# Schematic.net
KiCad netlist of a schematic drawn in Altium Designer
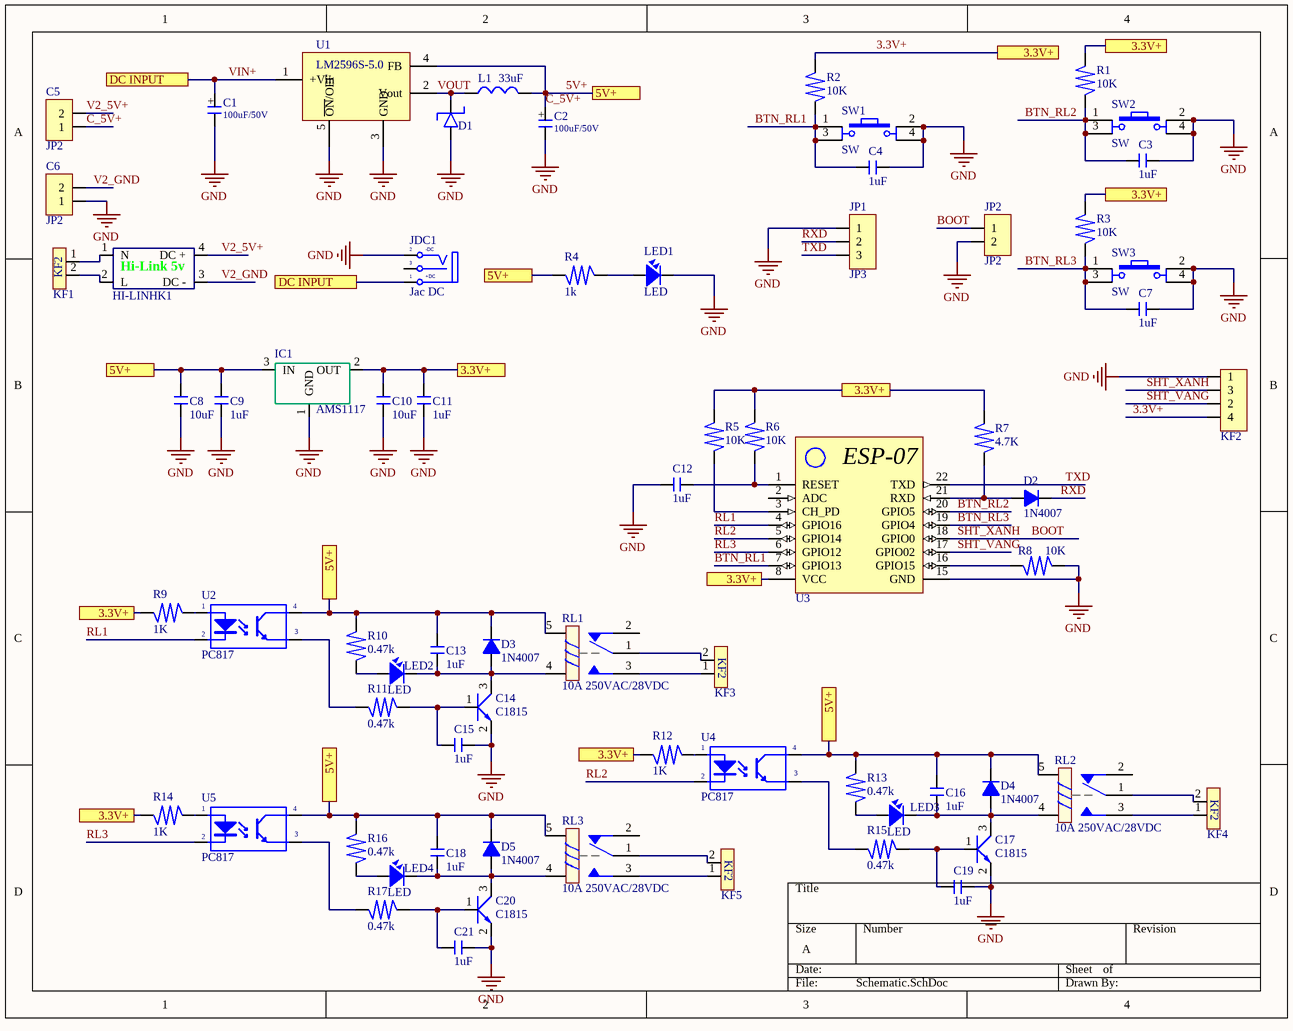
[diagram p0: Schematic.SchDoc]

(export (version "E")
  (design (tool "Eeschema 10.0.6"))
  (components
    (comp (ref "C1")
      (value "100uF/50V")
      (footprint "ALU D8x10")
      (description "100UF 50V, 20%, Size D=8mm, L=10mm")
      (fields (field (name "Comment") "CAP ALUM 100UF 50V 20% SMD"))
      (libsource (lib "LibSchQuocBao") (part "Alu 100uF/50v"))
    )
    (comp (ref "C2")
      (value "100uF/50V")
      (footprint "ALU D8x10")
      (description "100UF 50V, 20%, Size D=8mm, L=10mm")
      (fields (field (name "Comment") "CAP ALUM 100UF 50V 20% SMD"))
      (libsource (lib "LibSchQuocBao") (part "Alu 100uF/50v"))
    )
    (comp (ref "C3")
      (value "1uF")
      (footprint "C 0603(1608 metric)")
      (description "Capacitors Size SMD 0603")
      (libsource (lib "LibSchQuocBao") (part "CAP 0603 SMD"))
    )
    (comp (ref "C4")
      (value "1uF")
      (footprint "C 0603(1608 metric)")
      (description "Capacitors Size SMD 0603")
      (libsource (lib "LibSchQuocBao") (part "CAP 0603 SMD"))
    )
    (comp (ref "C5")
      (value "JP2")
      (footprint "JP2-CLOSED")
      (description "WR-PHD 2.54 mm Angled Socket Header")
      (fields
        (field (name "MANUFACTURER") "Würth Elektronik eiSos GmbH")
        (field (name "PARTNO") "613002143121")
        (field (name "CREATED BY") "Karrer Zheng")
      )
      (libsource (lib "LibSchQuocBao") (part "JP2"))
    )
    (comp (ref "C6")
      (value "JP2")
      (footprint "JP2-CLOSED")
      (description "WR-PHD 2.54 mm Angled Socket Header")
      (fields
        (field (name "MANUFACTURER") "Würth Elektronik eiSos GmbH")
        (field (name "PARTNO") "613002143121")
        (field (name "CREATED BY") "Karrer Zheng")
      )
      (libsource (lib "LibSchQuocBao") (part "JP2"))
    )
    (comp (ref "C7")
      (value "1uF")
      (footprint "C 0603(1608 metric)")
      (description "Capacitors Size SMD 0603")
      (libsource (lib "LibSchQuocBao") (part "CAP 0603 SMD"))
    )
    (comp (ref "C8")
      (value "10uF")
      (footprint "C 0603(1608 metric)")
      (description "Capacitors Size SMD 0603")
      (libsource (lib "LibSchQuocBao") (part "CAP 0603 SMD"))
    )
    (comp (ref "C9")
      (value "1uF")
      (footprint "C 0603(1608 metric)")
      (description "Capacitors Size SMD 0603")
      (libsource (lib "LibSchQuocBao") (part "CAP 0603 SMD"))
    )
    (comp (ref "C10")
      (value "10uF")
      (footprint "C 0603(1608 metric)")
      (description "Capacitors Size SMD 0603")
      (libsource (lib "LibSchQuocBao") (part "CAP 0603 SMD"))
    )
    (comp (ref "C11")
      (value "1uF")
      (footprint "C 0603(1608 metric)")
      (description "Capacitors Size SMD 0603")
      (libsource (lib "LibSchQuocBao") (part "CAP 0603 SMD"))
    )
    (comp (ref "C12")
      (value "1uF")
      (footprint "C 0603(1608 metric)")
      (description "Capacitors Size SMD 0603")
      (libsource (lib "LibSchQuocBao") (part "CAP 0603 SMD"))
    )
    (comp (ref "C13")
      (value "1uF")
      (footprint "C 0603(1608 metric)")
      (description "Capacitors Size SMD 0603")
      (libsource (lib "LibSchQuocBao") (part "CAP 0603 SMD"))
    )
    (comp (ref "C14")
      (value "C1815")
      (footprint "SOT23")
      (description "NPN ECB transistor, SOT23-3 package")
      (libsource (lib "LibSchQuocBao") (part "C1815 2SC1815-HF"))
    )
    (comp (ref "C15")
      (value "1uF")
      (footprint "C 0603(1608 metric)")
      (description "Capacitors Size SMD 0603")
      (libsource (lib "LibSchQuocBao") (part "CAP 0603 SMD"))
    )
    (comp (ref "C16")
      (value "1uF")
      (footprint "C 0603(1608 metric)")
      (description "Capacitors Size SMD 0603")
      (libsource (lib "LibSchQuocBao") (part "CAP 0603 SMD"))
    )
    (comp (ref "C17")
      (value "C1815")
      (footprint "SOT23")
      (description "NPN ECB transistor, SOT23-3 package")
      (libsource (lib "LibSchQuocBao") (part "C1815 2SC1815-HF"))
    )
    (comp (ref "C18")
      (value "1uF")
      (footprint "C 0603(1608 metric)")
      (description "Capacitors Size SMD 0603")
      (libsource (lib "LibSchQuocBao") (part "CAP 0603 SMD"))
    )
    (comp (ref "C19")
      (value "1uF")
      (footprint "C 0603(1608 metric)")
      (description "Capacitors Size SMD 0603")
      (libsource (lib "LibSchQuocBao") (part "CAP 0603 SMD"))
    )
    (comp (ref "C20")
      (value "C1815")
      (footprint "SOT23")
      (description "NPN ECB transistor, SOT23-3 package")
      (libsource (lib "LibSchQuocBao") (part "C1815 2SC1815-HF"))
    )
    (comp (ref "C21")
      (value "1uF")
      (footprint "C 0603(1608 metric)")
      (description "Capacitors Size SMD 0603")
      (libsource (lib "LibSchQuocBao") (part "CAP 0603 SMD"))
    )
    (comp (ref "D1")
      (value "SS34 SMA")
      (footprint "SS34-SMA")
      (description "Size A, DIODE SCHOTTKY 3A 40V SMA")
      (libsource (lib "LibSchQuocBao") (part "SS34 SMA"))
    )
    (comp (ref "D2")
      (value "1N4007")
      (footprint "SMA")
      (description "Diode 1A")
      (libsource (lib "LibSchQuocBao") (part "diode"))
    )
    (comp (ref "D3")
      (value "1N4007")
      (footprint "SMA")
      (description "Diode 1A")
      (libsource (lib "LibSchQuocBao") (part "diode"))
    )
    (comp (ref "D4")
      (value "1N4007")
      (footprint "SMA")
      (description "Diode 1A")
      (libsource (lib "LibSchQuocBao") (part "diode"))
    )
    (comp (ref "D5")
      (value "1N4007")
      (footprint "SMA")
      (description "Diode 1A")
      (libsource (lib "LibSchQuocBao") (part "diode"))
    )
    (comp (ref "HI-LINHK1")
      (value "Hi-link 5v")
      (footprint "Hi-Link")
      (libsource (lib "LibSchQuocBao") (part "Hi-link 5v"))
    )
    (comp (ref "IC1")
      (value "AMS1117")
      (footprint "AMS-1117")
      (libsource (lib "LibSchQuocBao") (part "AMS1117 3.3V"))
    )
    (comp (ref "JDC1")
      (value "Jac DC")
      (footprint "DC-IN")
      (description "Jac DC input")
      (libsource (lib "LibSchQuocBao") (part "DCIN"))
    )
    (comp (ref "JP1")
      (value "JP3")
      (footprint "JP3-D1T")
      (description "WR-PHD 2.54 mm Angled Socket Header")
      (fields
        (field (name "MANUFACTURER") "Würth Elektronik eiSos GmbH")
        (field (name "PARTNO") "613003143121")
        (field (name "CREATED BY") "Karrer Zheng")
      )
      (libsource (lib "LibSchQuocBao") (part "JP3"))
    )
    (comp (ref "JP2")
      (value "JP2")
      (footprint "JP2-CLOSED")
      (description "WR-PHD 2.54 mm Angled Socket Header")
      (fields
        (field (name "MANUFACTURER") "Würth Elektronik eiSos GmbH")
        (field (name "PARTNO") "613002143121")
        (field (name "CREATED BY") "Karrer Zheng")
      )
      (libsource (lib "") (part "JP2_1"))
    )
    (comp (ref "KF1")
      (value "Terminal Block 2Pin 5.08  KF2EDGK-5.08-2P-L")
      (footprint "KF2-7.62")
      (description "KF2 7.62")
      (libsource (lib "") (part "KF2_1"))
    )
    (comp (ref "KF2")
      (value "Terminal Block 4Pin 5.08  KF4EDGK-5.08-24-L")
      (footprint "HED4T")
      (libsource (lib "LibSchQuocBao") (part "KF4(KF4EDGK-5.08-4P-L)_1"))
    )
    (comp (ref "KF3")
      (value "Terminal Block 2Pin 5.08  KF2EDGK-5.08-2P-L")
      (footprint "KF2-7.62")
      (description "KF2 7.62")
      (libsource (lib "LibSchQuocBao") (part "KF2"))
    )
    (comp (ref "KF4")
      (value "Terminal Block 2Pin 5.08  KF2EDGK-5.08-2P-L")
      (footprint "KF2-7.62")
      (description "KF2 7.62")
      (libsource (lib "LibSchQuocBao") (part "KF2"))
    )
    (comp (ref "KF5")
      (value "Terminal Block 2Pin 5.08  KF2EDGK-5.08-2P-L")
      (footprint "KF2-7.62")
      (description "KF2 7.62")
      (libsource (lib "LibSchQuocBao") (part "KF2"))
    )
    (comp (ref "L1")
      (value "33uF")
      (footprint "RH127-471")
      (description "33UH (330) 3A, Size 12x12x7mm")
      (libsource (lib "LibSchQuocBao") (part "L 33UH RH127"))
    )
    (comp (ref "LED1")
      (value "LED")
      (footprint "LED-3")
      (description "LED Single colour Green and Red")
      (libsource (lib "LibSchQuocBao") (part "LED-DIP"))
    )
    (comp (ref "LED2")
      (value "LED")
      (footprint "LED-3")
      (description "LED Single colour Green and Red")
      (libsource (lib "LibSchQuocBao") (part "LED-DIP"))
    )
    (comp (ref "LED3")
      (value "LED")
      (footprint "LED-3")
      (description "LED Single colour Green and Red")
      (libsource (lib "LibSchQuocBao") (part "LED-DIP"))
    )
    (comp (ref "LED4")
      (value "LED")
      (footprint "LED-3")
      (description "LED Single colour Green and Red")
      (libsource (lib "LibSchQuocBao") (part "LED-DIP"))
    )
    (comp (ref "R1")
      (value "10K")
      (footprint "RES_0603")
      (description "SMD Resistor 3k OHM (Code 103) 1/8W 5% 0805 SMD")
      (fields (field (name "Comment") "RES 0.3K Ohm 0805 5%"))
      (libsource (lib "LibSchQuocBao") (part "R-0603-1k 5%"))
    )
    (comp (ref "R2")
      (value "10K")
      (footprint "RES_0603")
      (description "SMD Resistor 3k OHM (Code 103) 1/8W 5% 0805 SMD")
      (fields (field (name "Comment") "RES 0.3K Ohm 0805 5%"))
      (libsource (lib "LibSchQuocBao") (part "R-0603-1k 5%"))
    )
    (comp (ref "R3")
      (value "10K")
      (footprint "RES_0603")
      (description "SMD Resistor 3k OHM (Code 103) 1/8W 5% 0805 SMD")
      (fields (field (name "Comment") "RES 0.3K Ohm 0805 5%"))
      (libsource (lib "LibSchQuocBao") (part "R-0603-1k 5%"))
    )
    (comp (ref "R4")
      (value "1k")
      (footprint "RES_0603")
      (description "SMD Resistor 3k OHM (Code 103) 1/8W 5% 0805 SMD")
      (fields (field (name "Comment") "RES 0.3K Ohm 0805 5%"))
      (libsource (lib "LibSchQuocBao") (part "R-0603-1k 5%"))
    )
    (comp (ref "R5")
      (value "10K")
      (footprint "RES_0603")
      (description "SMD Resistor 3k OHM (Code 103) 1/8W 5% 0805 SMD")
      (fields (field (name "Comment") "RES 0.3K Ohm 0805 5%"))
      (libsource (lib "LibSchQuocBao") (part "R-0603-1k 5%"))
    )
    (comp (ref "R6")
      (value "10K")
      (footprint "RES_0603")
      (description "SMD Resistor 3k OHM (Code 103) 1/8W 5% 0805 SMD")
      (fields (field (name "Comment") "RES 0.3K Ohm 0805 5%"))
      (libsource (lib "LibSchQuocBao") (part "R-0603-1k 5%"))
    )
    (comp (ref "R7")
      (value "4.7K")
      (footprint "RES_0603")
      (description "SMD Resistor 3k OHM (Code 103) 1/8W 5% 0805 SMD")
      (fields (field (name "Comment") "RES 0.3K Ohm 0805 5%"))
      (libsource (lib "LibSchQuocBao") (part "R-0603-1k 5%"))
    )
    (comp (ref "R8")
      (value "10K")
      (footprint "RES_0603")
      (description "SMD Resistor 3k OHM (Code 103) 1/8W 5% 0805 SMD")
      (fields (field (name "Comment") "RES 0.3K Ohm 0805 5%"))
      (libsource (lib "LibSchQuocBao") (part "R-0603-1k 5%"))
    )
    (comp (ref "R9")
      (value "1K")
      (footprint "RES_0603")
      (description "SMD Resistor 3k OHM (Code 103) 1/8W 5% 0805 SMD")
      (fields (field (name "Comment") "RES 0.3K Ohm 0805 5%"))
      (libsource (lib "LibSchQuocBao") (part "R-0603-1k 5%"))
    )
    (comp (ref "R10")
      (value "0.47k")
      (footprint "RES_0603")
      (description "SMD Resistor 3k OHM (Code 103) 1/8W 5% 0805 SMD")
      (fields (field (name "Comment") "RES 0.3K Ohm 0805 5%"))
      (libsource (lib "LibSchQuocBao") (part "R-0603-1k 5%"))
    )
    (comp (ref "R11")
      (value "0.47k")
      (footprint "RES_0603")
      (description "SMD Resistor 3k OHM (Code 103) 1/8W 5% 0805 SMD")
      (fields (field (name "Comment") "RES 0.3K Ohm 0805 5%"))
      (libsource (lib "LibSchQuocBao") (part "R-0603-1k 5%"))
    )
    (comp (ref "R12")
      (value "1K")
      (footprint "RES_0603")
      (description "SMD Resistor 3k OHM (Code 103) 1/8W 5% 0805 SMD")
      (fields (field (name "Comment") "RES 0.3K Ohm 0805 5%"))
      (libsource (lib "LibSchQuocBao") (part "R-0603-1k 5%"))
    )
    (comp (ref "R13")
      (value "0.47k")
      (footprint "RES_0603")
      (description "SMD Resistor 3k OHM (Code 103) 1/8W 5% 0805 SMD")
      (fields (field (name "Comment") "RES 0.3K Ohm 0805 5%"))
      (libsource (lib "LibSchQuocBao") (part "R-0603-1k 5%"))
    )
    (comp (ref "R14")
      (value "1K")
      (footprint "RES_0603")
      (description "SMD Resistor 3k OHM (Code 103) 1/8W 5% 0805 SMD")
      (fields (field (name "Comment") "RES 0.3K Ohm 0805 5%"))
      (libsource (lib "LibSchQuocBao") (part "R-0603-1k 5%"))
    )
    (comp (ref "R15")
      (value "0.47k")
      (footprint "RES_0603")
      (description "SMD Resistor 3k OHM (Code 103) 1/8W 5% 0805 SMD")
      (fields (field (name "Comment") "RES 0.3K Ohm 0805 5%"))
      (libsource (lib "LibSchQuocBao") (part "R-0603-1k 5%"))
    )
    (comp (ref "R16")
      (value "0.47k")
      (footprint "RES_0603")
      (description "SMD Resistor 3k OHM (Code 103) 1/8W 5% 0805 SMD")
      (fields (field (name "Comment") "RES 0.3K Ohm 0805 5%"))
      (libsource (lib "LibSchQuocBao") (part "R-0603-1k 5%"))
    )
    (comp (ref "R17")
      (value "0.47k")
      (footprint "RES_0603")
      (description "SMD Resistor 3k OHM (Code 103) 1/8W 5% 0805 SMD")
      (fields (field (name "Comment") "RES 0.3K Ohm 0805 5%"))
      (libsource (lib "LibSchQuocBao") (part "R-0603-1k 5%"))
    )
    (comp (ref "RL1")
      (value "10A 250VAC/28VDC")
      (footprint "RL_SRD-5VDC")
      (description "5V DC SONGLE Power Relay SRD-05VDC-SL-C  (5 Pin mit NC / NO)")
      (libsource (lib "LibSchQuocBao") (part "Relay SRD-5VDC-SL-C"))
    )
    (comp (ref "RL2")
      (value "10A 250VAC/28VDC")
      (footprint "RL_SRD-5VDC")
      (description "5V DC SONGLE Power Relay SRD-05VDC-SL-C  (5 Pin mit NC / NO)")
      (libsource (lib "LibSchQuocBao") (part "Relay SRD-5VDC-SL-C"))
    )
    (comp (ref "RL3")
      (value "10A 250VAC/28VDC")
      (footprint "RL_SRD-5VDC")
      (description "5V DC SONGLE Power Relay SRD-05VDC-SL-C  (5 Pin mit NC / NO)")
      (libsource (lib "LibSchQuocBao") (part "Relay SRD-5VDC-SL-C"))
    )
    (comp (ref "SW1")
      (value "SW")
      (footprint "SW4")
      (description "Switch button 4 pin")
      (libsource (lib "LibSchQuocBao") (part "SW4"))
    )
    (comp (ref "SW2")
      (value "SW")
      (footprint "SW4")
      (description "Switch button 4 pin")
      (libsource (lib "LibSchQuocBao") (part "SW4"))
    )
    (comp (ref "SW3")
      (value "SW")
      (footprint "SW4")
      (description "Switch button 4 pin")
      (libsource (lib "LibSchQuocBao") (part "SW4"))
    )
    (comp (ref "U1")
      (value "IC REG BUCK 5V 3A TO263-5*")
      (footprint "TO263-5 - duplicate")
      (libsource (lib "LibSchQuocBao") (part "LM2596S-5.0"))
    )
    (comp (ref "U2")
      (value "PC817")
      (footprint "PC817_DIP")
      (description "Single Opto")
      (libsource (lib "LibSchQuocBao") (part "PC817"))
    )
    (comp (ref "U3")
      (value "ISM 2.4Ghz, 802.11 b/g/n, PA: +25dBm")
      (footprint "Esp-07")
      (libsource (lib "LibSchQuocBao") (part "ESP-7 ESP8266"))
    )
    (comp (ref "U4")
      (value "PC817")
      (footprint "PC817_DIP")
      (description "Single Opto")
      (libsource (lib "LibSchQuocBao") (part "PC817"))
    )
    (comp (ref "U5")
      (value "PC817")
      (footprint "PC817_DIP")
      (description "Single Opto")
      (libsource (lib "LibSchQuocBao") (part "PC817"))
    )
  )
  (nets
    (net (code "1") (name "/3.3V+") (class "Default")
      (node (ref "C10") (pin "2") (pinfunction "3_2") (pintype "passive"))
      (node (ref "C11") (pin "2") (pinfunction "3_2") (pintype "passive"))
      (node (ref "IC1") (pin "2") (pinfunction "OUT_2") (pintype "passive"))
      (node (ref "KF2") (pin "4") (pinfunction "4_4") (pintype "passive"))
      (node (ref "R1") (pin "2") (pinfunction "3_2") (pintype "passive"))
      (node (ref "R12") (pin "1") (pinfunction "1_1") (pintype "passive"))
      (node (ref "R14") (pin "1") (pinfunction "1_1") (pintype "passive"))
      (node (ref "R2") (pin "2") (pinfunction "3_2") (pintype "passive"))
      (node (ref "R3") (pin "2") (pinfunction "3_2") (pintype "passive"))
      (node (ref "R5") (pin "2") (pinfunction "3_2") (pintype "passive"))
      (node (ref "R6") (pin "2") (pinfunction "3_2") (pintype "passive"))
      (node (ref "R7") (pin "2") (pinfunction "3_2") (pintype "passive"))
      (node (ref "R9") (pin "1") (pinfunction "1_1") (pintype "passive"))
      (node (ref "U3") (pin "8") (pinfunction "VCC_8") (pintype "passive"))
    )
    (net (code "2") (name "/5V+") (class "Default")
      (node (ref "C13") (pin "2") (pinfunction "3_2") (pintype "passive"))
      (node (ref "C16") (pin "2") (pinfunction "3_2") (pintype "passive"))
      (node (ref "C18") (pin "2") (pinfunction "3_2") (pintype "passive"))
      (node (ref "C2") (pin "1") (pinfunction "+_1") (pintype "passive"))
      (node (ref "C5") (pin "1") (pinfunction "1_1") (pintype "passive"))
      (node (ref "C8") (pin "2") (pinfunction "3_2") (pintype "passive"))
      (node (ref "C9") (pin "2") (pinfunction "3_2") (pintype "passive"))
      (node (ref "D3") (pin "2") (pinfunction "K_2") (pintype "passive"))
      (node (ref "D4") (pin "2") (pinfunction "K_2") (pintype "passive"))
      (node (ref "D5") (pin "2") (pinfunction "K_2") (pintype "passive"))
      (node (ref "IC1") (pin "3") (pinfunction "IN_3") (pintype "passive"))
      (node (ref "L1") (pin "2") (pinfunction "2_2") (pintype "passive"))
      (node (ref "R10") (pin "2") (pinfunction "3_2") (pintype "passive"))
      (node (ref "R13") (pin "2") (pinfunction "3_2") (pintype "passive"))
      (node (ref "R16") (pin "2") (pinfunction "3_2") (pintype "passive"))
      (node (ref "R4") (pin "1") (pinfunction "1_1") (pintype "passive"))
      (node (ref "RL1") (pin "5") (pinfunction "5_5") (pintype "passive"))
      (node (ref "RL2") (pin "5") (pinfunction "5_5") (pintype "passive"))
      (node (ref "RL3") (pin "5") (pinfunction "5_5") (pintype "passive"))
      (node (ref "U1") (pin "4") (pinfunction "FB_4") (pintype "passive"))
      (node (ref "U2") (pin "4") (pinfunction "C_4") (pintype "passive"))
      (node (ref "U4") (pin "4") (pinfunction "C_4") (pintype "passive"))
      (node (ref "U5") (pin "4") (pinfunction "C_4") (pintype "passive"))
    )
    (net (code "3") (name "/BOOT") (class "Default")
      (node (ref "JP2") (pin "1") (pinfunction "1_1") (pintype "passive"))
      (node (ref "KF2") (pin "3") (pinfunction "3_3") (pintype "passive"))
      (node (ref "U3") (pin "18") (pinfunction "GPIO0_18") (pintype "bidirectional"))
    )
    (net (code "4") (name "/BTN_RL1") (class "Default")
      (node (ref "C4") (pin "1") (pinfunction "1_1") (pintype "passive"))
      (node (ref "R2") (pin "1") (pinfunction "1_1") (pintype "passive"))
      (node (ref "SW1") (pin "1") (pintype "passive"))
      (node (ref "SW1") (pin "3") (pintype "passive"))
      (node (ref "U3") (pin "7") (pinfunction "GPIO13_7") (pintype "bidirectional"))
    )
    (net (code "5") (name "/BTN_RL2") (class "Default")
      (node (ref "C3") (pin "1") (pinfunction "1_1") (pintype "passive"))
      (node (ref "R1") (pin "1") (pinfunction "1_1") (pintype "passive"))
      (node (ref "SW2") (pin "1") (pintype "passive"))
      (node (ref "SW2") (pin "3") (pintype "passive"))
      (node (ref "U3") (pin "20") (pinfunction "GPIO5_20") (pintype "bidirectional"))
    )
    (net (code "6") (name "/BTN_RL3") (class "Default")
      (node (ref "C7") (pin "1") (pinfunction "1_1") (pintype "passive"))
      (node (ref "R3") (pin "1") (pinfunction "1_1") (pintype "passive"))
      (node (ref "SW3") (pin "1") (pintype "passive"))
      (node (ref "SW3") (pin "3") (pintype "passive"))
      (node (ref "U3") (pin "19") (pinfunction "GPIO4_19") (pintype "bidirectional"))
    )
    (net (code "7") (name "/RL1") (class "Default")
      (node (ref "U2") (pin "2") (pinfunction "K_2") (pintype "passive"))
      (node (ref "U3") (pin "4") (pinfunction "GPIO16_4") (pintype "bidirectional"))
    )
    (net (code "8") (name "/RL2") (class "Default")
      (node (ref "U3") (pin "5") (pinfunction "GPIO14_5") (pintype "bidirectional"))
      (node (ref "U4") (pin "2") (pinfunction "K_2") (pintype "passive"))
    )
    (net (code "9") (name "/RL3") (class "Default")
      (node (ref "U3") (pin "6") (pinfunction "GPIO12_6") (pintype "bidirectional"))
      (node (ref "U5") (pin "2") (pinfunction "K_2") (pintype "passive"))
    )
    (net (code "10") (name "/RXD") (class "Default")
      (node (ref "D2") (pin "2") (pinfunction "K_2") (pintype "passive"))
      (node (ref "JP1") (pin "2") (pinfunction "2_2") (pintype "passive"))
    )
    (net (code "11") (name "/SHT_VANG") (class "Default")
      (node (ref "KF2") (pin "2") (pinfunction "2_2") (pintype "passive"))
      (node (ref "U3") (pin "17") (pinfunction "GPIO02_17") (pintype "bidirectional"))
    )
    (net (code "12") (name "/TXD") (class "Default")
      (node (ref "JP1") (pin "3") (pinfunction "3_3") (pintype "passive"))
      (node (ref "U3") (pin "22") (pinfunction "TXD_22") (pintype "output"))
    )
    (net (code "13") (name "/V2_5V+") (class "Default")
      (node (ref "C5") (pin "2") (pinfunction "2_2") (pintype "passive"))
      (node (ref "HI-LINHK1") (pin "4") (pinfunction "DC_+_4") (pintype "passive"))
    )
    (net (code "14") (name "/V2_GND") (class "Default")
      (node (ref "C6") (pin "2") (pinfunction "2_2") (pintype "passive"))
      (node (ref "HI-LINHK1") (pin "3") (pinfunction "DC_-_3") (pintype "passive"))
    )
    (net (code "15") (name "/VIN+") (class "Default")
      (node (ref "C1") (pin "1") (pinfunction "+_1") (pintype "passive"))
      (node (ref "JDC1") (pin "1") (pinfunction "T_1") (pintype "passive"))
      (node (ref "U1") (pin "1") (pinfunction "+Vin_1") (pintype "passive"))
    )
    (net (code "16") (name "/VOUT") (class "Default")
      (node (ref "D1") (pin "2") (pinfunction "2_2") (pintype "passive"))
      (node (ref "L1") (pin "1") (pinfunction "1_1") (pintype "passive"))
      (node (ref "U1") (pin "2") (pinfunction "Vout_2") (pintype "passive"))
    )
    (net (code "17") (name "GND") (class "Default")
      (node (ref "C1") (pin "2") (pinfunction "+_2") (pintype "passive"))
      (node (ref "C10") (pin "1") (pinfunction "1_1") (pintype "passive"))
      (node (ref "C11") (pin "1") (pinfunction "1_1") (pintype "passive"))
      (node (ref "C12") (pin "1") (pinfunction "1_1") (pintype "passive"))
      (node (ref "C14") (pin "2") (pinfunction "E_2") (pintype "passive"))
      (node (ref "C15") (pin "1") (pinfunction "1_1") (pintype "passive"))
      (node (ref "C17") (pin "2") (pinfunction "E_2") (pintype "passive"))
      (node (ref "C19") (pin "1") (pinfunction "1_1") (pintype "passive"))
      (node (ref "C2") (pin "2") (pinfunction "+_2") (pintype "passive"))
      (node (ref "C20") (pin "2") (pinfunction "E_2") (pintype "passive"))
      (node (ref "C21") (pin "1") (pinfunction "1_1") (pintype "passive"))
      (node (ref "C3") (pin "2") (pinfunction "3_2") (pintype "passive"))
      (node (ref "C4") (pin "2") (pinfunction "3_2") (pintype "passive"))
      (node (ref "C6") (pin "1") (pinfunction "1_1") (pintype "passive"))
      (node (ref "C7") (pin "2") (pinfunction "3_2") (pintype "passive"))
      (node (ref "C8") (pin "1") (pinfunction "1_1") (pintype "passive"))
      (node (ref "C9") (pin "1") (pinfunction "1_1") (pintype "passive"))
      (node (ref "D1") (pin "1") (pinfunction "1_1") (pintype "passive"))
      (node (ref "IC1") (pin "1") (pinfunction "GND_1") (pintype "passive"))
      (node (ref "JDC1") (pin "2") (pinfunction "TN_2") (pintype "passive"))
      (node (ref "JP1") (pin "1") (pinfunction "1_1") (pintype "passive"))
      (node (ref "JP2") (pin "2") (pinfunction "2_2") (pintype "passive"))
      (node (ref "KF2") (pin "1") (pinfunction "1_1") (pintype "passive"))
      (node (ref "LED1") (pin "2") (pinfunction "2_2") (pintype "passive"))
      (node (ref "R8") (pin "2") (pinfunction "3_2") (pintype "passive"))
      (node (ref "SW1") (pin "2") (pintype "passive"))
      (node (ref "SW1") (pin "4") (pintype "passive"))
      (node (ref "SW2") (pin "2") (pintype "passive"))
      (node (ref "SW2") (pin "4") (pintype "passive"))
      (node (ref "SW3") (pin "2") (pintype "passive"))
      (node (ref "SW3") (pin "4") (pintype "passive"))
      (node (ref "U1") (pin "3") (pinfunction "GND_3") (pintype "passive"))
      (node (ref "U1") (pin "5") (pinfunction "~{ON}/OFF_5") (pintype "passive"))
      (node (ref "U3") (pin "15") (pinfunction "GND_15") (pintype "passive"))
    )
    (net (code "18") (name "Net-(C12-3)") (class "Default")
      (node (ref "C12") (pin "2") (pinfunction "3_2") (pintype "passive"))
      (node (ref "R6") (pin "1") (pinfunction "1_1") (pintype "passive"))
      (node (ref "U3") (pin "1") (pinfunction "RESET_1") (pintype "passive"))
    )
    (net (code "19") (name "Net-(C14-B)") (class "Default")
      (node (ref "C14") (pin "1") (pinfunction "B_1") (pintype "passive"))
      (node (ref "C15") (pin "2") (pinfunction "3_2") (pintype "passive"))
      (node (ref "R11") (pin "1") (pinfunction "1_1") (pintype "passive"))
    )
    (net (code "20") (name "Net-(C14-C)") (class "Default")
      (node (ref "C13") (pin "1") (pinfunction "1_1") (pintype "passive"))
      (node (ref "C14") (pin "3") (pinfunction "C_3") (pintype "passive"))
      (node (ref "D3") (pin "1") (pinfunction "A_1") (pintype "passive"))
      (node (ref "LED2") (pin "2") (pinfunction "2_2") (pintype "passive"))
      (node (ref "RL1") (pin "4") (pinfunction "4_4") (pintype "passive"))
    )
    (net (code "21") (name "Net-(C17-B)") (class "Default")
      (node (ref "C17") (pin "1") (pinfunction "B_1") (pintype "passive"))
      (node (ref "C19") (pin "2") (pinfunction "3_2") (pintype "passive"))
      (node (ref "R15") (pin "1") (pinfunction "1_1") (pintype "passive"))
    )
    (net (code "22") (name "Net-(C17-C)") (class "Default")
      (node (ref "C16") (pin "1") (pinfunction "1_1") (pintype "passive"))
      (node (ref "C17") (pin "3") (pinfunction "C_3") (pintype "passive"))
      (node (ref "D4") (pin "1") (pinfunction "A_1") (pintype "passive"))
      (node (ref "LED3") (pin "2") (pinfunction "2_2") (pintype "passive"))
      (node (ref "RL2") (pin "4") (pinfunction "4_4") (pintype "passive"))
    )
    (net (code "23") (name "Net-(C20-B)") (class "Default")
      (node (ref "C20") (pin "1") (pinfunction "B_1") (pintype "passive"))
      (node (ref "C21") (pin "2") (pinfunction "3_2") (pintype "passive"))
      (node (ref "R17") (pin "1") (pinfunction "1_1") (pintype "passive"))
    )
    (net (code "24") (name "Net-(C20-C)") (class "Default")
      (node (ref "C18") (pin "1") (pinfunction "1_1") (pintype "passive"))
      (node (ref "C20") (pin "3") (pinfunction "C_3") (pintype "passive"))
      (node (ref "D5") (pin "1") (pinfunction "A_1") (pintype "passive"))
      (node (ref "LED4") (pin "2") (pinfunction "2_2") (pintype "passive"))
      (node (ref "RL3") (pin "4") (pinfunction "4_4") (pintype "passive"))
    )
    (net (code "25") (name "Net-(D2-A)") (class "Default")
      (node (ref "D2") (pin "1") (pinfunction "A_1") (pintype "passive"))
      (node (ref "R7") (pin "1") (pinfunction "1_1") (pintype "passive"))
      (node (ref "U3") (pin "21") (pinfunction "RXD_21") (pintype "input"))
    )
    (net (code "26") (name "Net-(HI-LINHK1-L)") (class "Default")
      (node (ref "HI-LINHK1") (pin "2") (pinfunction "L_2") (pintype "passive"))
      (node (ref "KF1") (pin "2") (pinfunction "3_2") (pintype "passive"))
    )
    (net (code "27") (name "Net-(HI-LINHK1-N)") (class "Default")
      (node (ref "HI-LINHK1") (pin "1") (pinfunction "N_1") (pintype "passive"))
      (node (ref "KF1") (pin "1") (pinfunction "1_1") (pintype "passive"))
    )
    (net (code "28") (name "Net-(KF3-3)") (class "Default")
      (node (ref "KF3") (pin "2") (pinfunction "3_2") (pintype "passive"))
      (node (ref "RL1") (pin "1") (pinfunction "1_1") (pintype "passive"))
    )
    (net (code "29") (name "Net-(KF3-Pad1)") (class "Default")
      (node (ref "KF3") (pin "1") (pinfunction "1_1") (pintype "passive"))
      (node (ref "RL1") (pin "3") (pinfunction "3_3") (pintype "passive"))
    )
    (net (code "30") (name "Net-(KF4-3)") (class "Default")
      (node (ref "KF4") (pin "2") (pinfunction "3_2") (pintype "passive"))
      (node (ref "RL2") (pin "1") (pinfunction "1_1") (pintype "passive"))
    )
    (net (code "31") (name "Net-(KF4-Pad1)") (class "Default")
      (node (ref "KF4") (pin "1") (pinfunction "1_1") (pintype "passive"))
      (node (ref "RL2") (pin "3") (pinfunction "3_3") (pintype "passive"))
    )
    (net (code "32") (name "Net-(KF5-3)") (class "Default")
      (node (ref "KF5") (pin "2") (pinfunction "3_2") (pintype "passive"))
      (node (ref "RL3") (pin "1") (pinfunction "1_1") (pintype "passive"))
    )
    (net (code "33") (name "Net-(KF5-Pad1)") (class "Default")
      (node (ref "KF5") (pin "1") (pinfunction "1_1") (pintype "passive"))
      (node (ref "RL3") (pin "3") (pinfunction "3_3") (pintype "passive"))
    )
    (net (code "34") (name "Net-(LED2-Pad1)") (class "Default")
      (node (ref "LED2") (pin "1") (pinfunction "1_1") (pintype "passive"))
      (node (ref "R10") (pin "1") (pinfunction "1_1") (pintype "passive"))
    )
    (net (code "35") (name "Net-(LED3-Pad1)") (class "Default")
      (node (ref "LED3") (pin "1") (pinfunction "1_1") (pintype "passive"))
      (node (ref "R13") (pin "1") (pinfunction "1_1") (pintype "passive"))
    )
    (net (code "36") (name "Net-(LED4-Pad1)") (class "Default")
      (node (ref "LED4") (pin "1") (pinfunction "1_1") (pintype "passive"))
      (node (ref "R16") (pin "1") (pinfunction "1_1") (pintype "passive"))
    )
    (net (code "37") (name "Net-(R4-3)") (class "Default")
      (node (ref "LED1") (pin "1") (pinfunction "1_1") (pintype "passive"))
      (node (ref "R4") (pin "2") (pinfunction "3_2") (pintype "passive"))
    )
    (net (code "38") (name "Net-(R9-3)") (class "Default")
      (node (ref "R9") (pin "2") (pinfunction "3_2") (pintype "passive"))
      (node (ref "U2") (pin "1") (pinfunction "A_1") (pintype "passive"))
    )
    (net (code "39") (name "Net-(R11-3)") (class "Default")
      (node (ref "R11") (pin "2") (pinfunction "3_2") (pintype "passive"))
      (node (ref "U2") (pin "3") (pinfunction "E_3") (pintype "passive"))
    )
    (net (code "40") (name "Net-(R12-3)") (class "Default")
      (node (ref "R12") (pin "2") (pinfunction "3_2") (pintype "passive"))
      (node (ref "U4") (pin "1") (pinfunction "A_1") (pintype "passive"))
    )
    (net (code "41") (name "Net-(R14-3)") (class "Default")
      (node (ref "R14") (pin "2") (pinfunction "3_2") (pintype "passive"))
      (node (ref "U5") (pin "1") (pinfunction "A_1") (pintype "passive"))
    )
    (net (code "42") (name "Net-(R15-3)") (class "Default")
      (node (ref "R15") (pin "2") (pinfunction "3_2") (pintype "passive"))
      (node (ref "U4") (pin "3") (pinfunction "E_3") (pintype "passive"))
    )
    (net (code "43") (name "Net-(R17-3)") (class "Default")
      (node (ref "R17") (pin "2") (pinfunction "3_2") (pintype "passive"))
      (node (ref "U5") (pin "3") (pinfunction "E_3") (pintype "passive"))
    )
    (net (code "44") (name "Net-(U3-CH_PD)") (class "Default")
      (node (ref "R5") (pin "1") (pinfunction "1_1") (pintype "passive"))
      (node (ref "U3") (pin "3") (pinfunction "CH_PD_3") (pintype "input"))
    )
    (net (code "45") (name "Net-(U3-GPIO15)") (class "Default")
      (node (ref "R8") (pin "1") (pinfunction "1_1") (pintype "passive"))
      (node (ref "U3") (pin "16") (pinfunction "GPIO15_16") (pintype "bidirectional"))
    )
    (net (code "46") (name "unconnected-(JDC1-S-Pad3)") (class "Default")
      (node (ref "JDC1") (pin "3") (pinfunction "S_3") (pintype "power_in"))
    )
    (net (code "47") (name "unconnected-(RL1-Pad2)") (class "Default")
      (node (ref "RL1") (pin "2") (pinfunction "2_2") (pintype "passive"))
    )
    (net (code "48") (name "unconnected-(RL2-Pad2)") (class "Default")
      (node (ref "RL2") (pin "2") (pinfunction "2_2") (pintype "passive"))
    )
    (net (code "49") (name "unconnected-(RL3-Pad2)") (class "Default")
      (node (ref "RL3") (pin "2") (pinfunction "2_2") (pintype "passive"))
    )
    (net (code "50") (name "unconnected-(U3-ADC-Pad2)") (class "Default")
      (node (ref "U3") (pin "2") (pinfunction "ADC_2") (pintype "input"))
    )
  )
)
